# power_motor_ver2.net
KiCad netlist of a schematic drawn in EAGLE
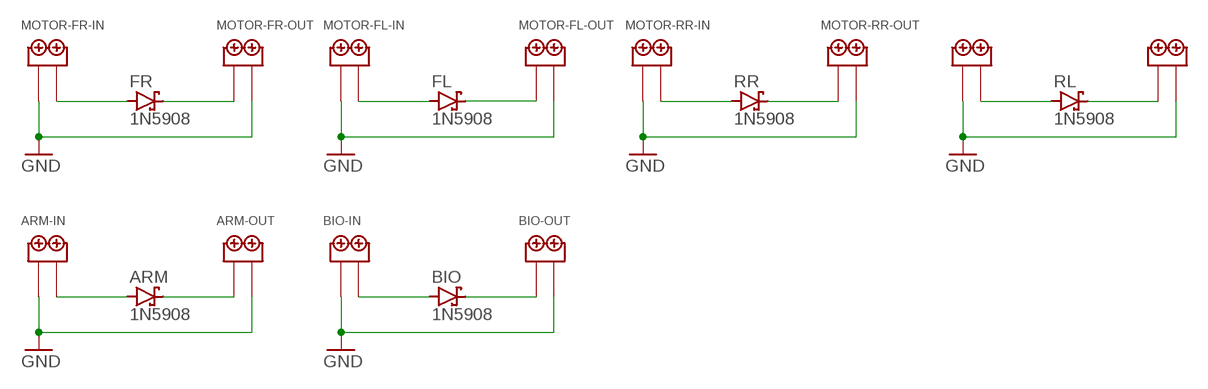
[diagram p0: schematic, sheet 1]

(export (version "E")
  (design (tool "Eeschema 10.0.6"))
  (components
    (comp (ref "ARM")
      (value "1N5908")
      (footprint "eagle-import:C4111-15")
      (libsource (lib "eagle-import") (part "1N5908"))
    )
    (comp (ref "ARM-IN")
      (value "2PIN")
      (footprint "eagle-import:2PIN")
      (libsource (lib "eagle-import") (part "2PIN"))
    )
    (comp (ref "ARM-OUT")
      (value "2PIN")
      (footprint "eagle-import:2PIN")
      (libsource (lib "eagle-import") (part "2PIN"))
    )
    (comp (ref "BIO")
      (value "1N5908")
      (footprint "eagle-import:C4111-15")
      (libsource (lib "eagle-import") (part "1N5908"))
    )
    (comp (ref "BIO-IN")
      (value "2PIN")
      (footprint "eagle-import:2PIN")
      (libsource (lib "eagle-import") (part "2PIN"))
    )
    (comp (ref "BIO-OUT")
      (value "2PIN")
      (footprint "eagle-import:2PIN")
      (libsource (lib "eagle-import") (part "2PIN"))
    )
    (comp (ref "FL")
      (value "1N5908")
      (footprint "eagle-import:C4111-15")
      (libsource (lib "eagle-import") (part "1N5908"))
    )
    (comp (ref "FR")
      (value "1N5908")
      (footprint "eagle-import:C4111-15")
      (libsource (lib "eagle-import") (part "1N5908"))
    )
    (comp (ref "MOTOR-FL-IN")
      (value "2PIN")
      (footprint "eagle-import:2PIN")
      (libsource (lib "eagle-import") (part "2PIN"))
    )
    (comp (ref "MOTOR-FL-OUT")
      (value "2PIN")
      (footprint "eagle-import:2PIN")
      (libsource (lib "eagle-import") (part "2PIN"))
    )
    (comp (ref "MOTOR-FR-IN")
      (value "2PIN")
      (footprint "eagle-import:2PIN")
      (libsource (lib "eagle-import") (part "2PIN"))
    )
    (comp (ref "MOTOR-FR-OUT")
      (value "2PIN")
      (footprint "eagle-import:2PIN")
      (libsource (lib "eagle-import") (part "2PIN"))
    )
    (comp (ref "MOTOR-RL-IN")
      (value "2PIN")
      (footprint "eagle-import:2PIN")
      (libsource (lib "eagle-import") (part "2PIN"))
    )
    (comp (ref "MOTOR-RL-OUT")
      (value "2PIN")
      (footprint "eagle-import:2PIN")
      (libsource (lib "eagle-import") (part "2PIN"))
    )
    (comp (ref "MOTOR-RR-IN")
      (value "2PIN")
      (footprint "eagle-import:2PIN")
      (libsource (lib "eagle-import") (part "2PIN"))
    )
    (comp (ref "MOTOR-RR-OUT")
      (value "2PIN")
      (footprint "eagle-import:2PIN")
      (libsource (lib "eagle-import") (part "2PIN"))
    )
    (comp (ref "RL")
      (value "1N5908")
      (footprint "eagle-import:C4111-15")
      (libsource (lib "eagle-import") (part "1N5908"))
    )
    (comp (ref "RR")
      (value "1N5908")
      (footprint "eagle-import:C4111-15")
      (libsource (lib "eagle-import") (part "1N5908"))
    )
  )
  (nets
    (net (code "1") (name "GND") (class "Default")
      (node (ref "ARM-IN") (pin "P$1") (pinfunction "P$1_P$1") (pintype "bidirectional"))
      (node (ref "ARM-OUT") (pin "P$2") (pinfunction "P$2_P$2") (pintype "bidirectional"))
      (node (ref "BIO-IN") (pin "P$1") (pinfunction "P$1_P$1") (pintype "bidirectional"))
      (node (ref "BIO-OUT") (pin "P$2") (pinfunction "P$2_P$2") (pintype "bidirectional"))
      (node (ref "MOTOR-FL-IN") (pin "P$1") (pinfunction "P$1_P$1") (pintype "bidirectional"))
      (node (ref "MOTOR-FL-OUT") (pin "P$2") (pinfunction "P$2_P$2") (pintype "bidirectional"))
      (node (ref "MOTOR-FR-IN") (pin "P$1") (pinfunction "P$1_P$1") (pintype "bidirectional"))
      (node (ref "MOTOR-FR-OUT") (pin "P$2") (pinfunction "P$2_P$2") (pintype "bidirectional"))
      (node (ref "MOTOR-RL-IN") (pin "P$1") (pinfunction "P$1_P$1") (pintype "bidirectional"))
      (node (ref "MOTOR-RL-OUT") (pin "P$2") (pinfunction "P$2_P$2") (pintype "bidirectional"))
      (node (ref "MOTOR-RR-IN") (pin "P$1") (pinfunction "P$1_P$1") (pintype "bidirectional"))
      (node (ref "MOTOR-RR-OUT") (pin "P$2") (pinfunction "P$2_P$2") (pintype "bidirectional"))
    )
    (net (code "2") (name "Net-(ARM-IN-PadP$2)") (class "Default")
      (node (ref "ARM") (pin "A") (pinfunction "A_A") (pintype "passive"))
      (node (ref "ARM-IN") (pin "P$2") (pinfunction "P$2_P$2") (pintype "bidirectional"))
    )
    (net (code "3") (name "Net-(ARM-OUT-PadP$1)") (class "Default")
      (node (ref "ARM") (pin "C") (pinfunction "C_C") (pintype "passive"))
      (node (ref "ARM-OUT") (pin "P$1") (pinfunction "P$1_P$1") (pintype "bidirectional"))
    )
    (net (code "4") (name "Net-(BIO-IN-PadP$2)") (class "Default")
      (node (ref "BIO") (pin "A") (pinfunction "A_A") (pintype "passive"))
      (node (ref "BIO-IN") (pin "P$2") (pinfunction "P$2_P$2") (pintype "bidirectional"))
    )
    (net (code "5") (name "Net-(BIO-OUT-PadP$1)") (class "Default")
      (node (ref "BIO") (pin "C") (pinfunction "C_C") (pintype "passive"))
      (node (ref "BIO-OUT") (pin "P$1") (pinfunction "P$1_P$1") (pintype "bidirectional"))
    )
    (net (code "6") (name "Net-(FL-PadA)") (class "Default")
      (node (ref "FL") (pin "A") (pinfunction "A_A") (pintype "passive"))
      (node (ref "MOTOR-FL-IN") (pin "P$2") (pinfunction "P$2_P$2") (pintype "bidirectional"))
    )
    (net (code "7") (name "Net-(FL-PadC)") (class "Default")
      (node (ref "FL") (pin "C") (pinfunction "C_C") (pintype "passive"))
      (node (ref "MOTOR-FL-OUT") (pin "P$1") (pinfunction "P$1_P$1") (pintype "bidirectional"))
    )
    (net (code "8") (name "Net-(FR-PadA)") (class "Default")
      (node (ref "FR") (pin "A") (pinfunction "A_A") (pintype "passive"))
      (node (ref "MOTOR-FR-IN") (pin "P$2") (pinfunction "P$2_P$2") (pintype "bidirectional"))
    )
    (net (code "9") (name "Net-(FR-PadC)") (class "Default")
      (node (ref "FR") (pin "C") (pinfunction "C_C") (pintype "passive"))
      (node (ref "MOTOR-FR-OUT") (pin "P$1") (pinfunction "P$1_P$1") (pintype "bidirectional"))
    )
    (net (code "10") (name "Net-(MOTOR-RL-IN-PadP$2)") (class "Default")
      (node (ref "MOTOR-RL-IN") (pin "P$2") (pinfunction "P$2_P$2") (pintype "bidirectional"))
      (node (ref "RL") (pin "A") (pinfunction "A_A") (pintype "passive"))
    )
    (net (code "11") (name "Net-(MOTOR-RL-OUT-PadP$1)") (class "Default")
      (node (ref "MOTOR-RL-OUT") (pin "P$1") (pinfunction "P$1_P$1") (pintype "bidirectional"))
      (node (ref "RL") (pin "C") (pinfunction "C_C") (pintype "passive"))
    )
    (net (code "12") (name "Net-(MOTOR-RR-IN-PadP$2)") (class "Default")
      (node (ref "MOTOR-RR-IN") (pin "P$2") (pinfunction "P$2_P$2") (pintype "bidirectional"))
      (node (ref "RR") (pin "A") (pinfunction "A_A") (pintype "passive"))
    )
    (net (code "13") (name "Net-(MOTOR-RR-OUT-PadP$1)") (class "Default")
      (node (ref "MOTOR-RR-OUT") (pin "P$1") (pinfunction "P$1_P$1") (pintype "bidirectional"))
      (node (ref "RR") (pin "C") (pinfunction "C_C") (pintype "passive"))
    )
  )
)
